# bh_gateway_alph.net
KiCad netlist of a schematic drawn in Altium Designer
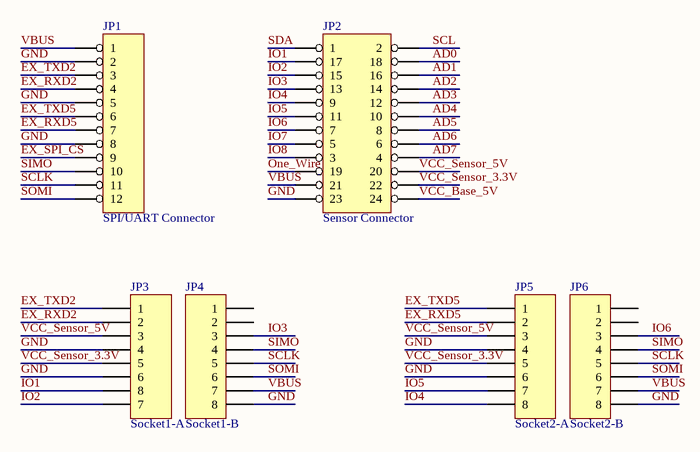
[diagram p0: bh_gateway_alph.SchDoc]

(export (version "E")
  (design (tool "Eeschema 10.0.6"))
  (components
    (comp (ref "JP1")
      (value "SPI/UART Connector")
      (footprint "SIP1x12x2.54")
      (description "单排排针直角")
      (libsource (lib "5D_CONNECTOR") (part "SIP1X12"))
    )
    (comp (ref "JP2")
      (value "Sensor Connector")
      (footprint "SIP2X12X2.54")
      (description "双排排针直角")
      (libsource (lib "5D_CONNECTOR") (part "SIP2X12"))
    )
    (comp (ref "JP3") (value "Socket1-A") (footprint "SIP1x8x2.0") (libsource (lib "") (part "SIP1X8_1")))
    (comp (ref "JP4")
      (value "Socket1-B")
      (footprint "SIP1x8x2.0")
      (description "8 Pin Header")
      (libsource (lib "") (part "SIP1X8_2"))
    )
    (comp (ref "JP5")
      (value "Socket2-A")
      (footprint "SIP1x8x2.0")
      (libsource (lib "5D_CONNECTOR") (part "SIP1X8"))
    )
    (comp (ref "JP6")
      (value "Socket2-B")
      (footprint "SIP1x8x2.0")
      (description "8 Pin Header")
      (libsource (lib "") (part "SIP1X8_2"))
    )
  )
  (nets
    (net (code "1") (name "/AD0") (class "Default")
      (node (ref "JP2") (pin "18") (pinfunction "18_18") (pintype "passive"))
    )
    (net (code "2") (name "/AD1") (class "Default")
      (node (ref "JP2") (pin "16") (pinfunction "16_16") (pintype "passive"))
    )
    (net (code "3") (name "/AD2") (class "Default")
      (node (ref "JP2") (pin "14") (pinfunction "14_14") (pintype "passive"))
    )
    (net (code "4") (name "/AD3") (class "Default")
      (node (ref "JP2") (pin "12") (pinfunction "12_12") (pintype "passive"))
    )
    (net (code "5") (name "/AD4") (class "Default")
      (node (ref "JP2") (pin "10") (pinfunction "10_10") (pintype "passive"))
    )
    (net (code "6") (name "/AD5") (class "Default")
      (node (ref "JP2") (pin "8") (pinfunction "8_8") (pintype "passive"))
    )
    (net (code "7") (name "/AD6") (class "Default")
      (node (ref "JP2") (pin "6") (pinfunction "6_6") (pintype "passive"))
    )
    (net (code "8") (name "/AD7") (class "Default")
      (node (ref "JP2") (pin "4") (pinfunction "4_4") (pintype "passive"))
    )
    (net (code "9") (name "/EX_RXD2") (class "Default")
      (node (ref "JP1") (pin "4") (pinfunction "4_4") (pintype "passive"))
      (node (ref "JP3") (pin "2") (pinfunction "2_2") (pintype "passive"))
    )
    (net (code "10") (name "/EX_RXD5") (class "Default")
      (node (ref "JP1") (pin "7") (pinfunction "7_7") (pintype "passive"))
      (node (ref "JP5") (pin "2") (pinfunction "2_2") (pintype "passive"))
    )
    (net (code "11") (name "/EX_SPI_CS") (class "Default")
      (node (ref "JP1") (pin "9") (pinfunction "9_9") (pintype "passive"))
    )
    (net (code "12") (name "/EX_TXD2") (class "Default")
      (node (ref "JP1") (pin "3") (pinfunction "3_3") (pintype "passive"))
      (node (ref "JP3") (pin "1") (pinfunction "1_1") (pintype "passive"))
    )
    (net (code "13") (name "/EX_TXD5") (class "Default")
      (node (ref "JP1") (pin "6") (pinfunction "6_6") (pintype "passive"))
      (node (ref "JP5") (pin "1") (pinfunction "1_1") (pintype "passive"))
    )
    (net (code "14") (name "/GND") (class "Default")
      (node (ref "JP1") (pin "2") (pinfunction "2_2") (pintype "passive"))
      (node (ref "JP1") (pin "5") (pinfunction "5_5") (pintype "passive"))
      (node (ref "JP1") (pin "8") (pinfunction "8_8") (pintype "passive"))
      (node (ref "JP2") (pin "23") (pinfunction "23_23") (pintype "passive"))
      (node (ref "JP3") (pin "4") (pinfunction "4_4") (pintype "passive"))
      (node (ref "JP3") (pin "6") (pinfunction "6_6") (pintype "passive"))
      (node (ref "JP4") (pin "8") (pinfunction "8_8") (pintype "passive"))
      (node (ref "JP5") (pin "4") (pinfunction "4_4") (pintype "passive"))
      (node (ref "JP5") (pin "6") (pinfunction "6_6") (pintype "passive"))
      (node (ref "JP6") (pin "8") (pinfunction "8_8") (pintype "passive"))
    )
    (net (code "15") (name "/IO1") (class "Default")
      (node (ref "JP2") (pin "17") (pinfunction "17_17") (pintype "passive"))
      (node (ref "JP3") (pin "8") (pinfunction "8_8") (pintype "passive"))
    )
    (net (code "16") (name "/IO2") (class "Default")
      (node (ref "JP2") (pin "15") (pinfunction "15_15") (pintype "passive"))
      (node (ref "JP3") (pin "7") (pinfunction "7_7") (pintype "passive"))
    )
    (net (code "17") (name "/IO3") (class "Default")
      (node (ref "JP2") (pin "13") (pinfunction "13_13") (pintype "passive"))
      (node (ref "JP4") (pin "3") (pinfunction "3_3") (pintype "passive"))
    )
    (net (code "18") (name "/IO4") (class "Default")
      (node (ref "JP2") (pin "9") (pinfunction "9_9") (pintype "passive"))
      (node (ref "JP5") (pin "8") (pinfunction "8_8") (pintype "passive"))
    )
    (net (code "19") (name "/IO5") (class "Default")
      (node (ref "JP2") (pin "11") (pinfunction "11_11") (pintype "passive"))
      (node (ref "JP5") (pin "7") (pinfunction "7_7") (pintype "passive"))
    )
    (net (code "20") (name "/IO6") (class "Default")
      (node (ref "JP2") (pin "7") (pinfunction "7_7") (pintype "passive"))
      (node (ref "JP6") (pin "3") (pinfunction "3_3") (pintype "passive"))
    )
    (net (code "21") (name "/IO7") (class "Default")
      (node (ref "JP2") (pin "5") (pinfunction "5_5") (pintype "passive"))
    )
    (net (code "22") (name "/IO8") (class "Default")
      (node (ref "JP2") (pin "3") (pinfunction "3_3") (pintype "passive"))
    )
    (net (code "23") (name "/One_Wire") (class "Default")
      (node (ref "JP2") (pin "19") (pinfunction "19_19") (pintype "passive"))
    )
    (net (code "24") (name "/SCL") (class "Default")
      (node (ref "JP2") (pin "2") (pinfunction "2_2") (pintype "passive"))
    )
    (net (code "25") (name "/SCLK") (class "Default")
      (node (ref "JP1") (pin "11") (pinfunction "11_11") (pintype "passive"))
      (node (ref "JP4") (pin "5") (pinfunction "5_5") (pintype "passive"))
      (node (ref "JP6") (pin "5") (pinfunction "5_5") (pintype "passive"))
    )
    (net (code "26") (name "/SDA") (class "Default")
      (node (ref "JP2") (pin "1") (pinfunction "1_1") (pintype "passive"))
    )
    (net (code "27") (name "/SIMO") (class "Default")
      (node (ref "JP1") (pin "10") (pinfunction "10_10") (pintype "passive"))
      (node (ref "JP4") (pin "4") (pinfunction "4_4") (pintype "passive"))
      (node (ref "JP6") (pin "4") (pinfunction "4_4") (pintype "passive"))
    )
    (net (code "28") (name "/SOMI") (class "Default")
      (node (ref "JP1") (pin "12") (pinfunction "12_12") (pintype "passive"))
      (node (ref "JP4") (pin "6") (pinfunction "6_6") (pintype "passive"))
      (node (ref "JP6") (pin "6") (pinfunction "6_6") (pintype "passive"))
    )
    (net (code "29") (name "/VBUS") (class "Default")
      (node (ref "JP1") (pin "1") (pinfunction "1_1") (pintype "passive"))
      (node (ref "JP2") (pin "21") (pinfunction "21_21") (pintype "passive"))
      (node (ref "JP4") (pin "7") (pinfunction "7_7") (pintype "passive"))
      (node (ref "JP6") (pin "7") (pinfunction "7_7") (pintype "passive"))
    )
    (net (code "30") (name "/VCC_Base_5V") (class "Default")
      (node (ref "JP2") (pin "24") (pinfunction "24_24") (pintype "passive"))
    )
    (net (code "31") (name "/VCC_Sensor_3.3V") (class "Default")
      (node (ref "JP2") (pin "22") (pinfunction "22_22") (pintype "passive"))
      (node (ref "JP3") (pin "5") (pinfunction "5_5") (pintype "passive"))
      (node (ref "JP5") (pin "5") (pinfunction "5_5") (pintype "passive"))
    )
    (net (code "32") (name "/VCC_Sensor_5V") (class "Default")
      (node (ref "JP2") (pin "20") (pinfunction "20_20") (pintype "passive"))
      (node (ref "JP3") (pin "3") (pinfunction "3_3") (pintype "passive"))
      (node (ref "JP5") (pin "3") (pinfunction "3_3") (pintype "passive"))
    )
    (net (code "33") (name "unconnected-(JP4-Pad1)") (class "Default")
      (node (ref "JP4") (pin "1") (pinfunction "1_1") (pintype "passive"))
    )
    (net (code "34") (name "unconnected-(JP4-Pad2)") (class "Default")
      (node (ref "JP4") (pin "2") (pinfunction "2_2") (pintype "passive"))
    )
    (net (code "35") (name "unconnected-(JP6-Pad1)") (class "Default")
      (node (ref "JP6") (pin "1") (pinfunction "1_1") (pintype "passive"))
    )
    (net (code "36") (name "unconnected-(JP6-Pad2)") (class "Default")
      (node (ref "JP6") (pin "2") (pinfunction "2_2") (pintype "passive"))
    )
  )
)
